# main.net
KiCad netlist of a schematic drawn in Altium Designer
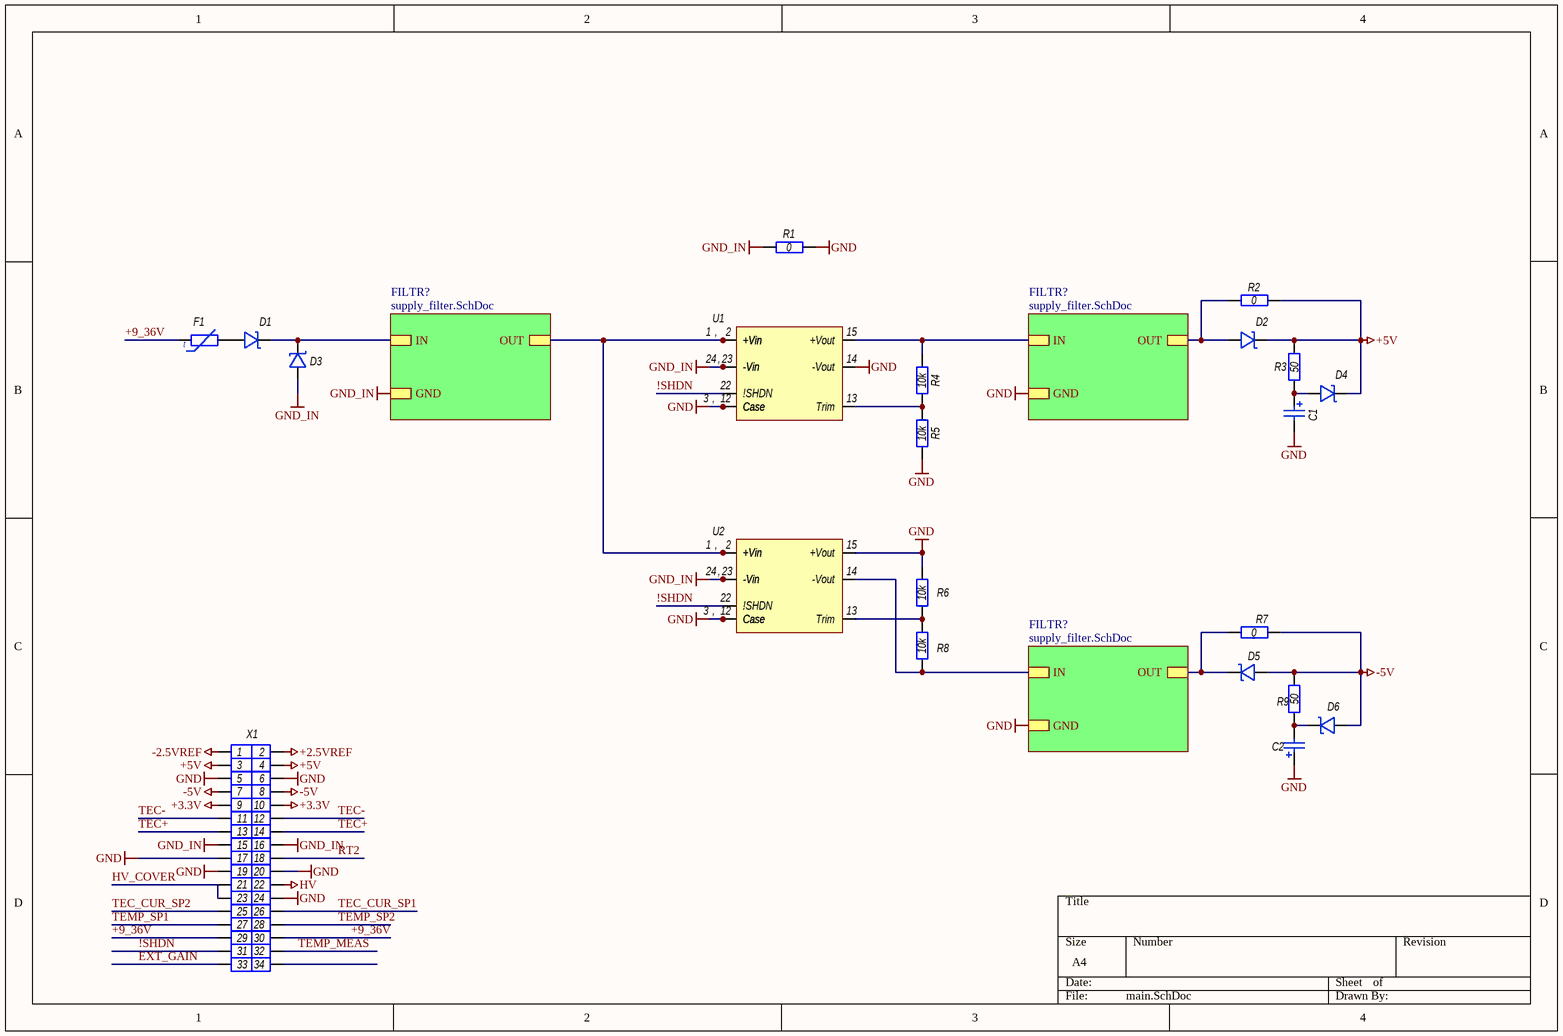
[diagram p0: main.SchDoc]

(export (version "E")
  (design (tool "Eeschema 10.0.6"))
  (components
    (comp (ref "C1")
      (value "47u 63V")
      (description "Конденсатор электролитический")
      (libsource (lib "SCH_LIB") (part "CapacitorEl"))
    )
    (comp (ref "C2")
      (value "47u 63V")
      (description "Конденсатор электролитический")
      (libsource (lib "SCH_LIB") (part "CapacitorEl"))
    )
    (comp (ref "D1")
      (value "VS-15MQ040")
      (footprint "DO-214AC (SMA)")
      (description "Диод Шоттки")
      (libsource (lib "SCH_LIB") (part "MBR0520"))
    )
    (comp (ref "D2")
      (value "VS-15MQ040")
      (footprint "DO-214AC (SMA)")
      (description "Диод Шоттки")
      (libsource (lib "SCH_LIB") (part "MBR0520"))
    )
    (comp (ref "D3")
      (value "VS-15MQ040")
      (footprint "DO-214AC (SMA)")
      (description "Диод Шоттки")
      (libsource (lib "SCH_LIB") (part "MBR0520"))
    )
    (comp (ref "D4")
      (value "VS-15MQ040")
      (footprint "DO-214AC (SMA)")
      (description "Диод Шоттки")
      (libsource (lib "SCH_LIB") (part "MBR0520"))
    )
    (comp (ref "D5")
      (value "VS-15MQ040")
      (footprint "DO-214AC (SMA)")
      (description "Диод Шоттки")
      (libsource (lib "SCH_LIB") (part "MBR0520"))
    )
    (comp (ref "D6")
      (value "VS-15MQ040")
      (footprint "DO-214AC (SMA)")
      (description "Диод Шоттки")
      (libsource (lib "SCH_LIB") (part "MBR0520"))
    )
    (comp (ref "F1")
      (value "MF-NSMF035")
      (footprint "PCB_LIB:RES_1206")
      (description "Предохранитель самовосстанавливаемый")
      (libsource (lib "SCH_LIB") (part "MF-NSMFxxx"))
    )
    (comp (ref "R1")
      (value "0")
      (footprint "RES_0603")
      (description "Резистор")
      (libsource (lib "SCH_LIB") (part "Resisitor"))
    )
    (comp (ref "R2")
      (value "0")
      (footprint "RES_0603")
      (description "Резистор")
      (libsource (lib "SCH_LIB") (part "Resisitor"))
    )
    (comp (ref "R3")
      (value "50")
      (footprint "RES_0603")
      (description "Резистор")
      (libsource (lib "SCH_LIB") (part "Resisitor"))
    )
    (comp (ref "R4")
      (value "10k")
      (footprint "RES_0603")
      (description "Резистор")
      (libsource (lib "SCH_LIB") (part "Resisitor"))
    )
    (comp (ref "R5")
      (value "10k")
      (footprint "RES_0603")
      (description "Резистор")
      (libsource (lib "SCH_LIB") (part "Resisitor"))
    )
    (comp (ref "R6")
      (value "10k")
      (footprint "RES_0603")
      (description "Резистор")
      (libsource (lib "SCH_LIB") (part "Resisitor"))
    )
    (comp (ref "R7")
      (value "0")
      (footprint "RES_0603")
      (description "Резистор")
      (libsource (lib "SCH_LIB") (part "Resisitor"))
    )
    (comp (ref "R8")
      (value "10k")
      (footprint "RES_0603")
      (description "Резистор")
      (libsource (lib "SCH_LIB") (part "Resisitor"))
    )
    (comp (ref "R9")
      (value "50")
      (footprint "RES_0603")
      (description "Резистор")
      (libsource (lib "SCH_LIB") (part "Resisitor"))
    )
    (comp (ref "U1")
      (value "TWN 5")
      (footprint "DCDC_TVN")
      (description "DC/DC модуль питания")
      (libsource (lib "SCH_LIB") (part "TWN 5"))
    )
    (comp (ref "U2")
      (value "TWN 5")
      (footprint "DCDC_TVN")
      (description "DC/DC модуль питания")
      (libsource (lib "SCH_LIB") (part "TWN 5"))
    )
    (comp (ref "X1") (value "?") (footprint "BH-34") (libsource (lib "SCH_LIB") (part "Connector 17x2")))
  )
  (nets
    (net (code "1") (name "+2.5VREF") (class "Default")
      (node (ref "X1") (pin "2") (pinfunction "2_2") (pintype "passive"))
    )
    (net (code "2") (name "+3.3V") (class "Default")
      (node (ref "X1") (pin "10") (pinfunction "10_10") (pintype "passive"))
      (node (ref "X1") (pin "9") (pinfunction "9_9") (pintype "passive"))
    )
    (net (code "3") (name "+5V") (class "Default")
      (node (ref "D2") (pin "2") (pintype "passive"))
      (node (ref "D4") (pin "2") (pintype "passive"))
      (node (ref "R2") (pin "2") (pinfunction "2_2") (pintype "passive"))
      (node (ref "R3") (pin "1") (pinfunction "1_1") (pintype "passive"))
      (node (ref "X1") (pin "3") (pinfunction "3_3") (pintype "passive"))
      (node (ref "X1") (pin "4") (pinfunction "4_4") (pintype "passive"))
    )
    (net (code "4") (name "-2.5VREF") (class "Default")
      (node (ref "X1") (pin "1") (pinfunction "1_1") (pintype "passive"))
    )
    (net (code "5") (name "-5V") (class "Default")
      (node (ref "D5") (pin "1") (pintype "passive"))
      (node (ref "D6") (pin "1") (pintype "passive"))
      (node (ref "R7") (pin "2") (pinfunction "2_2") (pintype "passive"))
      (node (ref "R9") (pin "1") (pinfunction "1_1") (pintype "passive"))
      (node (ref "X1") (pin "7") (pinfunction "7_7") (pintype "passive"))
      (node (ref "X1") (pin "8") (pinfunction "8_8") (pintype "passive"))
    )
    (net (code "6") (name "/!SHDN") (class "Default")
      (node (ref "U1") (pin "22") (pinfunction "!SHDN_22") (pintype "passive"))
      (node (ref "U2") (pin "22") (pinfunction "!SHDN_22") (pintype "passive"))
      (node (ref "X1") (pin "31") (pinfunction "31_31") (pintype "passive"))
    )
    (net (code "7") (name "/+9_36V") (class "Default")
      (node (ref "F1") (pin "1") (pinfunction "1_1") (pintype "passive"))
      (node (ref "X1") (pin "29") (pinfunction "29_29") (pintype "passive"))
      (node (ref "X1") (pin "30") (pinfunction "30_30") (pintype "passive"))
    )
    (net (code "8") (name "/EXT_GAIN") (class "Default")
      (node (ref "X1") (pin "33") (pinfunction "33_33") (pintype "passive"))
    )
    (net (code "9") (name "/HV_COVER") (class "Default")
      (node (ref "X1") (pin "21") (pinfunction "21_21") (pintype "passive"))
      (node (ref "X1") (pin "23") (pinfunction "23_23") (pintype "passive"))
    )
    (net (code "10") (name "/IN") (class "Default")
      (node (ref "R4") (pin "1") (pinfunction "1_1") (pintype "passive"))
      (node (ref "U1") (pin "15") (pinfunction "+Vout_15") (pintype "passive"))
    )
    (net (code "11") (name "/IN_1") (class "Default")
      (node (ref "D1") (pin "2") (pintype "passive"))
      (node (ref "D3") (pin "2") (pintype "passive"))
    )
    (net (code "12") (name "/IN_2") (class "Default")
      (node (ref "R8") (pin "2") (pinfunction "2_2") (pintype "passive"))
      (node (ref "U2") (pin "14") (pinfunction "-Vout_14") (pintype "passive"))
    )
    (net (code "13") (name "/OUT") (class "Default")
      (node (ref "D2") (pin "1") (pintype "passive"))
      (node (ref "R2") (pin "1") (pinfunction "1_1") (pintype "passive"))
    )
    (net (code "14") (name "/OUT_1") (class "Default")
      (node (ref "U1") (pin "1") (pinfunction "+Vin_1") (pintype "passive"))
      (node (ref "U1") (pin "2") (pinfunction "+Vin_2") (pintype "passive"))
      (node (ref "U2") (pin "1") (pinfunction "+Vin_1") (pintype "passive"))
      (node (ref "U2") (pin "2") (pinfunction "+Vin_2") (pintype "passive"))
    )
    (net (code "15") (name "/OUT_2") (class "Default")
      (node (ref "D5") (pin "2") (pintype "passive"))
      (node (ref "R7") (pin "1") (pinfunction "1_1") (pintype "passive"))
    )
    (net (code "16") (name "/RT2") (class "Default")
      (node (ref "X1") (pin "18") (pinfunction "18_18") (pintype "passive"))
    )
    (net (code "17") (name "/TEC+") (class "Default")
      (node (ref "X1") (pin "13") (pinfunction "13_13") (pintype "passive"))
      (node (ref "X1") (pin "14") (pinfunction "14_14") (pintype "passive"))
    )
    (net (code "18") (name "/TEC-") (class "Default")
      (node (ref "X1") (pin "11") (pinfunction "11_11") (pintype "passive"))
      (node (ref "X1") (pin "12") (pinfunction "12_12") (pintype "passive"))
    )
    (net (code "19") (name "/TEC_CUR_SP1") (class "Default")
      (node (ref "X1") (pin "26") (pinfunction "26_26") (pintype "passive"))
    )
    (net (code "20") (name "/TEC_CUR_SP2") (class "Default")
      (node (ref "X1") (pin "25") (pinfunction "25_25") (pintype "passive"))
    )
    (net (code "21") (name "/TEMP_MEAS") (class "Default")
      (node (ref "X1") (pin "32") (pinfunction "32_32") (pintype "passive"))
    )
    (net (code "22") (name "/TEMP_SP1") (class "Default")
      (node (ref "X1") (pin "27") (pinfunction "27_27") (pintype "passive"))
    )
    (net (code "23") (name "/TEMP_SP2") (class "Default")
      (node (ref "X1") (pin "28") (pinfunction "28_28") (pintype "passive"))
    )
    (net (code "24") (name "GND") (class "Default")
      (node (ref "C1") (pin "2") (pinfunction "2_2") (pintype "passive"))
      (node (ref "C2") (pin "1") (pinfunction "1_1") (pintype "passive"))
      (node (ref "R1") (pin "2") (pinfunction "2_2") (pintype "passive"))
      (node (ref "R5") (pin "2") (pinfunction "2_2") (pintype "passive"))
      (node (ref "R6") (pin "1") (pinfunction "1_1") (pintype "passive"))
      (node (ref "U1") (pin "12") (pinfunction "Case_12") (pintype "passive"))
      (node (ref "U1") (pin "14") (pinfunction "-Vout_14") (pintype "passive"))
      (node (ref "U1") (pin "3") (pinfunction "Case_3") (pintype "passive"))
      (node (ref "U2") (pin "12") (pinfunction "Case_12") (pintype "passive"))
      (node (ref "U2") (pin "15") (pinfunction "+Vout_15") (pintype "passive"))
      (node (ref "U2") (pin "3") (pinfunction "Case_3") (pintype "passive"))
      (node (ref "X1") (pin "17") (pinfunction "17_17") (pintype "passive"))
      (node (ref "X1") (pin "19") (pinfunction "19_19") (pintype "passive"))
      (node (ref "X1") (pin "20") (pinfunction "20_20") (pintype "passive"))
      (node (ref "X1") (pin "24") (pinfunction "24_24") (pintype "passive"))
      (node (ref "X1") (pin "5") (pinfunction "5_5") (pintype "passive"))
      (node (ref "X1") (pin "6") (pinfunction "6_6") (pintype "passive"))
    )
    (net (code "25") (name "GND_IN") (class "Default")
      (node (ref "D3") (pin "1") (pintype "passive"))
      (node (ref "R1") (pin "1") (pinfunction "1_1") (pintype "passive"))
      (node (ref "U1") (pin "23") (pinfunction "-Vin_23") (pintype "passive"))
      (node (ref "U1") (pin "24") (pinfunction "-Vin_24") (pintype "passive"))
      (node (ref "U2") (pin "23") (pinfunction "-Vin_23") (pintype "passive"))
      (node (ref "U2") (pin "24") (pinfunction "-Vin_24") (pintype "passive"))
      (node (ref "X1") (pin "15") (pinfunction "15_15") (pintype "passive"))
      (node (ref "X1") (pin "16") (pinfunction "16_16") (pintype "passive"))
    )
    (net (code "26") (name "HV") (class "Default")
      (node (ref "X1") (pin "22") (pinfunction "22_22") (pintype "passive"))
    )
    (net (code "27") (name "Net-(C1-Pad1)") (class "Default")
      (node (ref "C1") (pin "1") (pinfunction "1_1") (pintype "passive"))
      (node (ref "D4") (pin "1") (pintype "passive"))
      (node (ref "R3") (pin "2") (pinfunction "2_2") (pintype "passive"))
    )
    (net (code "28") (name "Net-(C2-Pad2)") (class "Default")
      (node (ref "C2") (pin "2") (pinfunction "2_2") (pintype "passive"))
      (node (ref "D6") (pin "2") (pintype "passive"))
      (node (ref "R9") (pin "2") (pinfunction "2_2") (pintype "passive"))
    )
    (net (code "29") (name "Net-(D1-Pad1)") (class "Default")
      (node (ref "D1") (pin "1") (pintype "passive"))
      (node (ref "F1") (pin "2") (pinfunction "2_2") (pintype "passive"))
    )
    (net (code "30") (name "Net-(U1-Trim)") (class "Default")
      (node (ref "R4") (pin "2") (pinfunction "2_2") (pintype "passive"))
      (node (ref "R5") (pin "1") (pinfunction "1_1") (pintype "passive"))
      (node (ref "U1") (pin "13") (pinfunction "Trim_13") (pintype "passive"))
    )
    (net (code "31") (name "Net-(U2-Trim)") (class "Default")
      (node (ref "R6") (pin "2") (pinfunction "2_2") (pintype "passive"))
      (node (ref "R8") (pin "1") (pinfunction "1_1") (pintype "passive"))
      (node (ref "U2") (pin "13") (pinfunction "Trim_13") (pintype "passive"))
    )
    (net (code "32") (name "unconnected-(X1-Pad34)") (class "Default")
      (node (ref "X1") (pin "34") (pinfunction "34_34") (pintype "passive"))
    )
  )
)
